# Bluetooth.net
KiCad netlist of a schematic drawn in Altium Designer
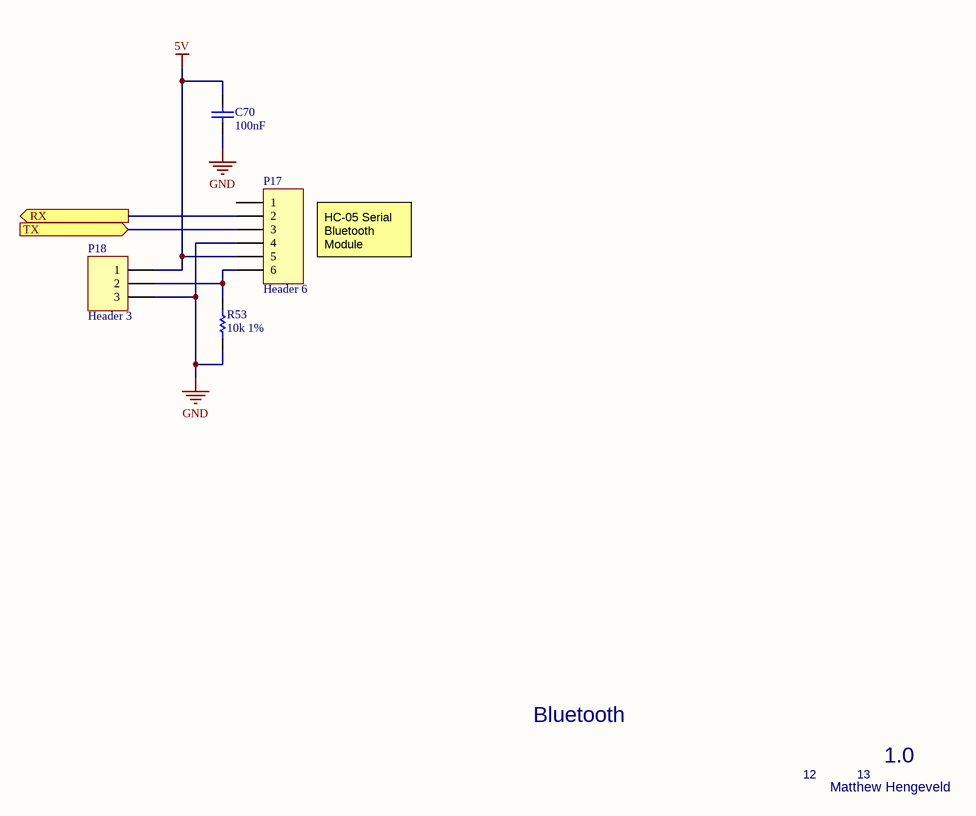
[diagram p0: Bluetooth.SchDoc]

(export (version "E")
  (design (tool "Eeschema 10.0.6"))
  (components
    (comp (ref "C70")
      (value "100nF")
      (footprint "CAPC1608X92X38LL15T08")
      (fields (field (name "PART NUMBER") "VJ0603Y104KNXAO") (field (name "MANUFACTURER") "Vitramon"))
      (libsource (lib "Altium Content Vault") (part "CAP"))
    )
    (comp (ref "P17")
      (value "Header 6")
      (footprint "HDR1X6")
      (description "Header, 6-Pin")
      (fields (field (name "PUBLISHER") "Altium Limited"))
      (libsource (lib "Hengeveld") (part "Header 6"))
    )
    (comp (ref "P18")
      (value "Header 3")
      (footprint "HDR1X3")
      (description "Header, 3-Pin")
      (fields (field (name "PUBLISHER") "Altium Limited"))
      (libsource (lib "Hengeveld") (part "Header 3"))
    )
    (comp (ref "R53")
      (value "10k 1%")
      (footprint "RESC1608X55X30LL15T15")
      (fields (field (name "PART NUMBER") "ERJ-3EKF1002V") (field (name "MANUFACTURER") "Panasonic"))
      (libsource (lib "Altium Content Vault") (part "RES"))
    )
  )
  (nets
    (net (code "1") (name "/RX") (class "Default")
      (node (ref "P17") (pin "2") (pinfunction "2_2") (pintype "passive"))
    )
    (net (code "2") (name "/TX") (class "Default")
      (node (ref "P17") (pin "3") (pinfunction "3_3") (pintype "passive"))
    )
    (net (code "3") (name "5V") (class "Default")
      (node (ref "C70") (pin "1") (pinfunction "1_1") (pintype "passive"))
      (node (ref "P17") (pin "5") (pinfunction "5_5") (pintype "passive"))
      (node (ref "P18") (pin "1") (pinfunction "1_1") (pintype "passive"))
    )
    (net (code "4") (name "GND") (class "Default")
      (node (ref "C70") (pin "2") (pinfunction "2_2") (pintype "passive"))
      (node (ref "P17") (pin "4") (pinfunction "4_4") (pintype "passive"))
      (node (ref "P18") (pin "3") (pinfunction "3_3") (pintype "passive"))
      (node (ref "R53") (pin "1") (pinfunction "1_1") (pintype "passive"))
    )
    (net (code "5") (name "Net-(P17-Pad6)") (class "Default")
      (node (ref "P17") (pin "6") (pinfunction "6_6") (pintype "passive"))
      (node (ref "P18") (pin "2") (pinfunction "2_2") (pintype "passive"))
      (node (ref "R53") (pin "2") (pinfunction "2_2") (pintype "passive"))
    )
    (net (code "6") (name "unconnected-(P17-Pad1)") (class "Default")
      (node (ref "P17") (pin "1") (pinfunction "1_1") (pintype "passive"))
    )
  )
)
